# 3_3volt_rail.net
KiCad netlist of a schematic drawn in EAGLE
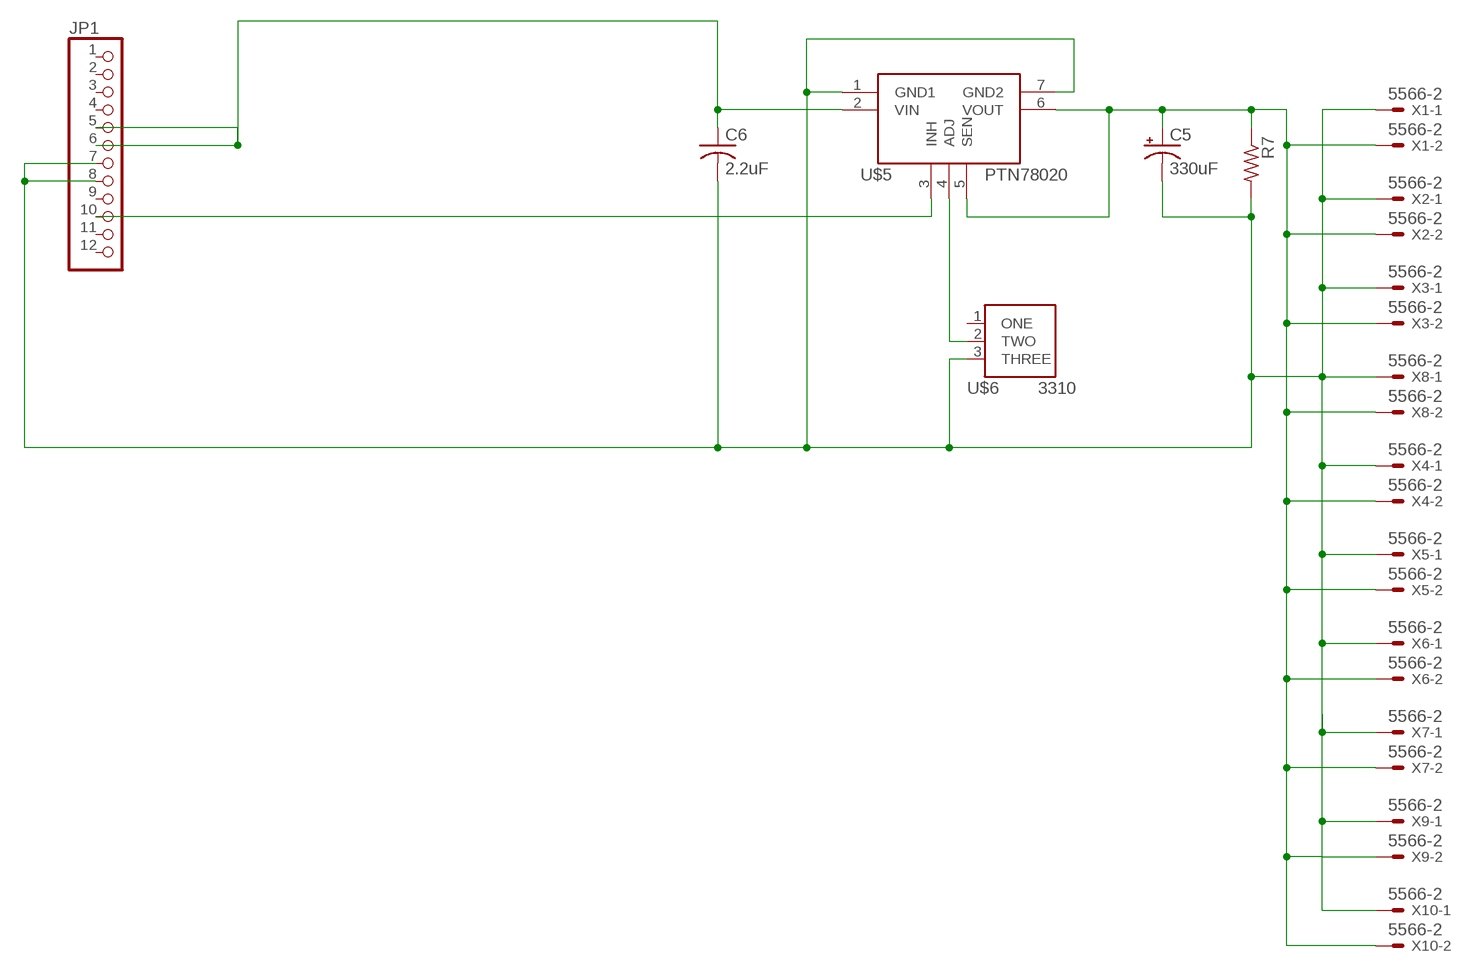
[diagram p0: schematic, sheet 1]

(export (version "E")
  (design (tool "Eeschema 10.0.6"))
  (components
    (comp (ref "C5")
      (value "330uF")
      (footprint "eagle-import:E5-10,5")
      (libsource (lib "eagle-import") (part "CPOL-USE5-10.5"))
    )
    (comp (ref "C6")
      (value "2.2uF")
      (footprint "eagle-import:C0805")
      (libsource (lib "eagle-import") (part "C-USC0805"))
    )
    (comp (ref "JP1")
      (value "PINHD-1X12")
      (footprint "eagle-import:1X12")
      (libsource (lib "eagle-import") (part "PINHD-1X12"))
    )
    (comp (ref "R7")
      (value "R-US_M0805")
      (footprint "eagle-import:M0805")
      (libsource (lib "eagle-import") (part "R-US_M0805"))
    )
    (comp (ref "U$5")
      (value "PTH78020-SMD")
      (footprint "eagle-import:PTN78020-SND")
      (libsource (lib "eagle-import") (part "PTH78020-SMD"))
    )
    (comp (ref "U$6")
      (value "3310-001")
      (footprint "eagle-import:3310-001-TH")
      (libsource (lib "eagle-import") (part "3310-001"))
    )
    (comp (ref "X1")
      (value "5566-2")
      (footprint "eagle-import:5566-2")
      (libsource (lib "eagle-import") (part "5566-2"))
    )
    (comp (ref "X2")
      (value "5566-2")
      (footprint "eagle-import:5566-2")
      (libsource (lib "eagle-import") (part "5566-2"))
    )
    (comp (ref "X3")
      (value "5566-2")
      (footprint "eagle-import:5566-2")
      (libsource (lib "eagle-import") (part "5566-2"))
    )
    (comp (ref "X4")
      (value "5566-2")
      (footprint "eagle-import:5566-2")
      (libsource (lib "eagle-import") (part "5566-2"))
    )
    (comp (ref "X5")
      (value "5566-2")
      (footprint "eagle-import:5566-2")
      (libsource (lib "eagle-import") (part "5566-2"))
    )
    (comp (ref "X6")
      (value "5566-2")
      (footprint "eagle-import:5566-2")
      (libsource (lib "eagle-import") (part "5566-2"))
    )
    (comp (ref "X7")
      (value "5566-2")
      (footprint "eagle-import:5566-2")
      (libsource (lib "eagle-import") (part "5566-2"))
    )
    (comp (ref "X8")
      (value "5566-2")
      (footprint "eagle-import:5566-2")
      (libsource (lib "eagle-import") (part "5566-2"))
    )
    (comp (ref "X9")
      (value "5566-2")
      (footprint "eagle-import:5566-2")
      (libsource (lib "eagle-import") (part "5566-2"))
    )
    (comp (ref "X10")
      (value "5566-2")
      (footprint "eagle-import:5566-2")
      (libsource (lib "eagle-import") (part "5566-2"))
    )
  )
  (nets
    (net (code "1") (name "Net-(U$5-ADJ)") (class "Default")
      (node (ref "U$5") (pin "4") (pinfunction "ADJ_4") (pintype "bidirectional"))
      (node (ref "U$6") (pin "2") (pinfunction "TWO_2") (pintype "bidirectional"))
    )
    (net (code "2") (name "Net-(U$5-GND1)") (class "Default")
      (node (ref "C5") (pin "-") (pinfunction "-_-") (pintype "passive"))
      (node (ref "C6") (pin "2") (pinfunction "2_2") (pintype "passive"))
      (node (ref "JP1") (pin "7") (pinfunction "7_7") (pintype "passive"))
      (node (ref "JP1") (pin "8") (pinfunction "8_8") (pintype "passive"))
      (node (ref "R7") (pin "2") (pinfunction "2_2") (pintype "passive"))
      (node (ref "U$5") (pin "1") (pinfunction "GND1_1") (pintype "bidirectional"))
      (node (ref "U$5") (pin "7") (pinfunction "GND2_7") (pintype "bidirectional"))
      (node (ref "U$6") (pin "3") (pinfunction "THREE_3") (pintype "bidirectional"))
      (node (ref "X1") (pin "1") (pinfunction "S_1") (pintype "passive"))
      (node (ref "X10") (pin "1") (pinfunction "S_1") (pintype "passive"))
      (node (ref "X2") (pin "1") (pinfunction "S_1") (pintype "passive"))
      (node (ref "X3") (pin "1") (pinfunction "S_1") (pintype "passive"))
      (node (ref "X4") (pin "1") (pinfunction "S_1") (pintype "passive"))
      (node (ref "X5") (pin "1") (pinfunction "S_1") (pintype "passive"))
      (node (ref "X6") (pin "1") (pinfunction "S_1") (pintype "passive"))
      (node (ref "X7") (pin "1") (pinfunction "S_1") (pintype "passive"))
      (node (ref "X8") (pin "1") (pinfunction "S_1") (pintype "passive"))
      (node (ref "X9") (pin "1") (pinfunction "S_1") (pintype "passive"))
    )
    (net (code "3") (name "Net-(U$5-INH)") (class "Default")
      (node (ref "JP1") (pin "10") (pinfunction "10_10") (pintype "passive"))
      (node (ref "U$5") (pin "3") (pinfunction "INH_3") (pintype "bidirectional"))
    )
    (net (code "4") (name "Net-(U$5-SEN)") (class "Default")
      (node (ref "C5") (pin "+") (pinfunction "+_+") (pintype "passive"))
      (node (ref "R7") (pin "1") (pinfunction "1_1") (pintype "passive"))
      (node (ref "U$5") (pin "5") (pinfunction "SEN_5") (pintype "bidirectional"))
      (node (ref "U$5") (pin "6") (pinfunction "VOUT_6") (pintype "bidirectional"))
      (node (ref "X1") (pin "2") (pinfunction "S_2") (pintype "passive"))
      (node (ref "X10") (pin "2") (pinfunction "S_2") (pintype "passive"))
      (node (ref "X2") (pin "2") (pinfunction "S_2") (pintype "passive"))
      (node (ref "X3") (pin "2") (pinfunction "S_2") (pintype "passive"))
      (node (ref "X4") (pin "2") (pinfunction "S_2") (pintype "passive"))
      (node (ref "X5") (pin "2") (pinfunction "S_2") (pintype "passive"))
      (node (ref "X6") (pin "2") (pinfunction "S_2") (pintype "passive"))
      (node (ref "X7") (pin "2") (pinfunction "S_2") (pintype "passive"))
      (node (ref "X8") (pin "2") (pinfunction "S_2") (pintype "passive"))
      (node (ref "X9") (pin "2") (pinfunction "S_2") (pintype "passive"))
    )
    (net (code "5") (name "Net-(U$5-VIN)") (class "Default")
      (node (ref "C6") (pin "1") (pinfunction "1_1") (pintype "passive"))
      (node (ref "JP1") (pin "5") (pinfunction "5_5") (pintype "passive"))
      (node (ref "JP1") (pin "6") (pinfunction "6_6") (pintype "passive"))
      (node (ref "U$5") (pin "2") (pinfunction "VIN_2") (pintype "bidirectional"))
    )
    (net (code "6") (name "unconnected-(JP1-Pad1)") (class "Default")
      (node (ref "JP1") (pin "1") (pinfunction "1_1") (pintype "passive"))
    )
    (net (code "7") (name "unconnected-(JP1-Pad2)") (class "Default")
      (node (ref "JP1") (pin "2") (pinfunction "2_2") (pintype "passive"))
    )
    (net (code "8") (name "unconnected-(JP1-Pad3)") (class "Default")
      (node (ref "JP1") (pin "3") (pinfunction "3_3") (pintype "passive"))
    )
    (net (code "9") (name "unconnected-(JP1-Pad4)") (class "Default")
      (node (ref "JP1") (pin "4") (pinfunction "4_4") (pintype "passive"))
    )
    (net (code "10") (name "unconnected-(JP1-Pad9)") (class "Default")
      (node (ref "JP1") (pin "9") (pinfunction "9_9") (pintype "passive"))
    )
    (net (code "11") (name "unconnected-(JP1-Pad11)") (class "Default")
      (node (ref "JP1") (pin "11") (pinfunction "11_11") (pintype "passive"))
    )
    (net (code "12") (name "unconnected-(JP1-Pad12)") (class "Default")
      (node (ref "JP1") (pin "12") (pinfunction "12_12") (pintype "passive"))
    )
    (net (code "13") (name "unconnected-(U$6-ONE-Pad1)") (class "Default")
      (node (ref "U$6") (pin "1") (pinfunction "ONE_1") (pintype "bidirectional"))
    )
  )
)
